# Cool-unitV2.net
KiCad netlist of a schematic drawn in EAGLE
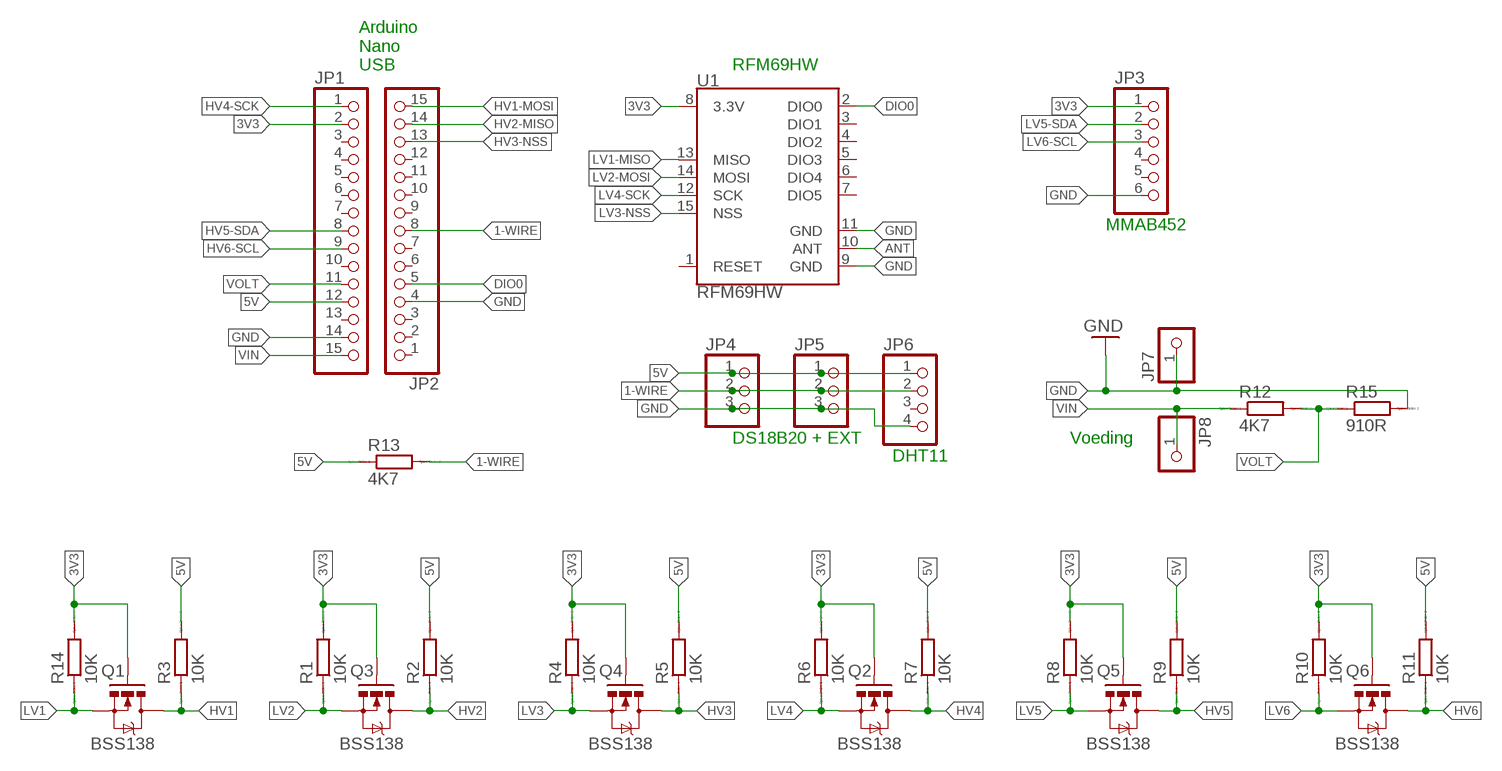
[diagram p0: schematic, sheet 1]

(export (version "E")
  (design (tool "Eeschema 10.0.6"))
  (components
    (comp (ref "JP1")
      (value "PINHD-1X15")
      (footprint "eagle-import:1X15")
      (libsource (lib "eagle-import") (part "PINHD-1X15"))
    )
    (comp (ref "JP2")
      (value "PINHD-1X15")
      (footprint "eagle-import:1X15")
      (libsource (lib "eagle-import") (part "PINHD-1X15"))
    )
    (comp (ref "JP3")
      (value "PINHD-1X6")
      (footprint "eagle-import:1X06")
      (libsource (lib "eagle-import") (part "PINHD-1X6"))
    )
    (comp (ref "JP4")
      (value "PINHD-1X3")
      (footprint "eagle-import:1X03")
      (libsource (lib "eagle-import") (part "PINHD-1X3"))
    )
    (comp (ref "JP5")
      (value "PINHD-1X3")
      (footprint "eagle-import:1X03")
      (libsource (lib "eagle-import") (part "PINHD-1X3"))
    )
    (comp (ref "JP6")
      (value "PINHD-1X4")
      (footprint "eagle-import:1X04")
      (libsource (lib "eagle-import") (part "PINHD-1X4"))
    )
    (comp (ref "JP7")
      (value "PINHD-1X1")
      (footprint "eagle-import:1X01")
      (libsource (lib "eagle-import") (part "PINHD-1X1"))
    )
    (comp (ref "JP8")
      (value "PINHD-1X1")
      (footprint "eagle-import:1X01")
      (libsource (lib "eagle-import") (part "PINHD-1X1"))
    )
    (comp (ref "Q1")
      (value "BSS138")
      (footprint "eagle-import:SOT23-3")
      (libsource (lib "eagle-import") (part "MOSFET-NCHANNELSMD"))
    )
    (comp (ref "Q2")
      (value "BSS138")
      (footprint "eagle-import:SOT23-3")
      (libsource (lib "eagle-import") (part "MOSFET-NCHANNELSMD"))
    )
    (comp (ref "Q3")
      (value "BSS138")
      (footprint "eagle-import:SOT23-3")
      (libsource (lib "eagle-import") (part "MOSFET-NCHANNELSMD"))
    )
    (comp (ref "Q4")
      (value "BSS138")
      (footprint "eagle-import:SOT23-3")
      (libsource (lib "eagle-import") (part "MOSFET-NCHANNELSMD"))
    )
    (comp (ref "Q5")
      (value "BSS138")
      (footprint "eagle-import:SOT23-3")
      (libsource (lib "eagle-import") (part "MOSFET-NCHANNELSMD"))
    )
    (comp (ref "Q6")
      (value "BSS138")
      (footprint "eagle-import:SOT23-3")
      (libsource (lib "eagle-import") (part "MOSFET-NCHANNELSMD"))
    )
    (comp (ref "R1")
      (value "10K")
      (footprint "eagle-import:R3216")
      (libsource (lib "eagle-import") (part "RR3216"))
    )
    (comp (ref "R2")
      (value "10K")
      (footprint "eagle-import:R3216")
      (libsource (lib "eagle-import") (part "RR3216"))
    )
    (comp (ref "R3")
      (value "10K")
      (footprint "eagle-import:R3216")
      (libsource (lib "eagle-import") (part "RR3216"))
    )
    (comp (ref "R4")
      (value "10K")
      (footprint "eagle-import:R3216")
      (libsource (lib "eagle-import") (part "RR3216"))
    )
    (comp (ref "R5")
      (value "10K")
      (footprint "eagle-import:R3216")
      (libsource (lib "eagle-import") (part "RR3216"))
    )
    (comp (ref "R6")
      (value "10K")
      (footprint "eagle-import:R3216")
      (libsource (lib "eagle-import") (part "RR3216"))
    )
    (comp (ref "R7")
      (value "10K")
      (footprint "eagle-import:R3216")
      (libsource (lib "eagle-import") (part "RR3216"))
    )
    (comp (ref "R8")
      (value "10K")
      (footprint "eagle-import:R3216")
      (libsource (lib "eagle-import") (part "RR3216"))
    )
    (comp (ref "R9")
      (value "10K")
      (footprint "eagle-import:R3216")
      (libsource (lib "eagle-import") (part "RR3216"))
    )
    (comp (ref "R10")
      (value "10K")
      (footprint "eagle-import:R3216")
      (libsource (lib "eagle-import") (part "RR3216"))
    )
    (comp (ref "R11")
      (value "10K")
      (footprint "eagle-import:R3216")
      (libsource (lib "eagle-import") (part "RR3216"))
    )
    (comp (ref "R12")
      (value "4K7")
      (footprint "eagle-import:R3216")
      (libsource (lib "eagle-import") (part "RR3216"))
    )
    (comp (ref "R13")
      (value "4K7")
      (footprint "eagle-import:R3216")
      (libsource (lib "eagle-import") (part "RR3216"))
    )
    (comp (ref "R14")
      (value "10K")
      (footprint "eagle-import:R3216")
      (libsource (lib "eagle-import") (part "RR3216"))
    )
    (comp (ref "R15")
      (value "910R")
      (footprint "eagle-import:R3216")
      (libsource (lib "eagle-import") (part "RR3216"))
    )
    (comp (ref "U1")
      (value "RFM69HW")
      (footprint "eagle-import:RFM69W-XXXS2")
      (libsource (lib "eagle-import") (part "RFM69HW"))
    )
  )
  (nets
    (net (code "1") (name "1-WIRE") (class "Default")
      (node (ref "JP2") (pin "8") (pinfunction "8_8") (pintype "passive"))
      (node (ref "JP4") (pin "2") (pinfunction "2_2") (pintype "passive"))
      (node (ref "JP5") (pin "2") (pinfunction "2_2") (pintype "passive"))
      (node (ref "JP6") (pin "2") (pinfunction "2_2") (pintype "passive"))
      (node (ref "R13") (pin "2") (pinfunction "2_2") (pintype "passive"))
    )
    (net (code "2") (name "3V3") (class "Default")
      (node (ref "JP1") (pin "2") (pinfunction "2_2") (pintype "passive"))
      (node (ref "JP3") (pin "1") (pinfunction "1_1") (pintype "passive"))
      (node (ref "Q1") (pin "1") (pinfunction "G_1") (pintype "passive"))
      (node (ref "Q2") (pin "1") (pinfunction "G_1") (pintype "passive"))
      (node (ref "Q3") (pin "1") (pinfunction "G_1") (pintype "passive"))
      (node (ref "Q4") (pin "1") (pinfunction "G_1") (pintype "passive"))
      (node (ref "Q5") (pin "1") (pinfunction "G_1") (pintype "passive"))
      (node (ref "Q6") (pin "1") (pinfunction "G_1") (pintype "passive"))
      (node (ref "R1") (pin "2") (pinfunction "2_2") (pintype "passive"))
      (node (ref "R10") (pin "2") (pinfunction "2_2") (pintype "passive"))
      (node (ref "R14") (pin "2") (pinfunction "2_2") (pintype "passive"))
      (node (ref "R4") (pin "2") (pinfunction "2_2") (pintype "passive"))
      (node (ref "R6") (pin "2") (pinfunction "2_2") (pintype "passive"))
      (node (ref "R8") (pin "2") (pinfunction "2_2") (pintype "passive"))
      (node (ref "U1") (pin "8") (pinfunction "3.3V_8") (pintype "power_in"))
    )
    (net (code "3") (name "5V") (class "Default")
      (node (ref "JP1") (pin "12") (pinfunction "12_12") (pintype "passive"))
      (node (ref "JP4") (pin "1") (pinfunction "1_1") (pintype "passive"))
      (node (ref "JP5") (pin "1") (pinfunction "1_1") (pintype "passive"))
      (node (ref "JP6") (pin "1") (pinfunction "1_1") (pintype "passive"))
      (node (ref "R11") (pin "2") (pinfunction "2_2") (pintype "passive"))
      (node (ref "R13") (pin "1") (pinfunction "1_1") (pintype "passive"))
      (node (ref "R2") (pin "2") (pinfunction "2_2") (pintype "passive"))
      (node (ref "R3") (pin "2") (pinfunction "2_2") (pintype "passive"))
      (node (ref "R5") (pin "2") (pinfunction "2_2") (pintype "passive"))
      (node (ref "R7") (pin "2") (pinfunction "2_2") (pintype "passive"))
      (node (ref "R9") (pin "2") (pinfunction "2_2") (pintype "passive"))
    )
    (net (code "4") (name "ANT") (class "Default")
      (node (ref "U1") (pin "10") (pinfunction "ANT_10") (pintype "passive"))
    )
    (net (code "5") (name "DIO0") (class "Default")
      (node (ref "JP2") (pin "5") (pinfunction "5_5") (pintype "passive"))
      (node (ref "U1") (pin "2") (pinfunction "DIO0_2") (pintype "bidirectional"))
    )
    (net (code "6") (name "GND") (class "Default")
      (node (ref "JP1") (pin "14") (pinfunction "14_14") (pintype "passive"))
      (node (ref "JP2") (pin "4") (pinfunction "4_4") (pintype "passive"))
      (node (ref "JP3") (pin "6") (pinfunction "6_6") (pintype "passive"))
      (node (ref "JP4") (pin "3") (pinfunction "3_3") (pintype "passive"))
      (node (ref "JP5") (pin "3") (pinfunction "3_3") (pintype "passive"))
      (node (ref "JP6") (pin "4") (pinfunction "4_4") (pintype "passive"))
      (node (ref "JP7") (pin "1") (pinfunction "1_1") (pintype "passive"))
      (node (ref "R15") (pin "2") (pinfunction "2_2") (pintype "passive"))
      (node (ref "U1") (pin "11") (pinfunction "GND_11") (pintype "power_in"))
      (node (ref "U1") (pin "9") (pinfunction "GND_9") (pintype "power_in"))
    )
    (net (code "7") (name "HV1") (class "Default")
      (node (ref "JP2") (pin "15") (pinfunction "15_15") (pintype "passive"))
      (node (ref "Q1") (pin "3") (pinfunction "D_3") (pintype "passive"))
      (node (ref "R3") (pin "1") (pinfunction "1_1") (pintype "passive"))
    )
    (net (code "8") (name "HV2") (class "Default")
      (node (ref "JP2") (pin "14") (pinfunction "14_14") (pintype "passive"))
      (node (ref "Q3") (pin "3") (pinfunction "D_3") (pintype "passive"))
      (node (ref "R2") (pin "1") (pinfunction "1_1") (pintype "passive"))
    )
    (net (code "9") (name "HV3") (class "Default")
      (node (ref "JP2") (pin "13") (pinfunction "13_13") (pintype "passive"))
      (node (ref "Q4") (pin "3") (pinfunction "D_3") (pintype "passive"))
      (node (ref "R5") (pin "1") (pinfunction "1_1") (pintype "passive"))
    )
    (net (code "10") (name "HV4") (class "Default")
      (node (ref "JP1") (pin "1") (pinfunction "1_1") (pintype "passive"))
      (node (ref "Q2") (pin "3") (pinfunction "D_3") (pintype "passive"))
      (node (ref "R7") (pin "1") (pinfunction "1_1") (pintype "passive"))
    )
    (net (code "11") (name "HV5") (class "Default")
      (node (ref "JP1") (pin "8") (pinfunction "8_8") (pintype "passive"))
      (node (ref "Q5") (pin "3") (pinfunction "D_3") (pintype "passive"))
      (node (ref "R9") (pin "1") (pinfunction "1_1") (pintype "passive"))
    )
    (net (code "12") (name "HV6") (class "Default")
      (node (ref "JP1") (pin "9") (pinfunction "9_9") (pintype "passive"))
      (node (ref "Q6") (pin "3") (pinfunction "D_3") (pintype "passive"))
      (node (ref "R11") (pin "1") (pinfunction "1_1") (pintype "passive"))
    )
    (net (code "13") (name "LV1") (class "Default")
      (node (ref "Q1") (pin "2") (pinfunction "S_2") (pintype "passive"))
      (node (ref "R14") (pin "1") (pinfunction "1_1") (pintype "passive"))
      (node (ref "U1") (pin "13") (pinfunction "MISO_13") (pintype "bidirectional"))
    )
    (net (code "14") (name "LV2") (class "Default")
      (node (ref "Q3") (pin "2") (pinfunction "S_2") (pintype "passive"))
      (node (ref "R1") (pin "1") (pinfunction "1_1") (pintype "passive"))
      (node (ref "U1") (pin "14") (pinfunction "MOSI_14") (pintype "input"))
    )
    (net (code "15") (name "LV3") (class "Default")
      (node (ref "Q4") (pin "2") (pinfunction "S_2") (pintype "passive"))
      (node (ref "R4") (pin "1") (pinfunction "1_1") (pintype "passive"))
      (node (ref "U1") (pin "15") (pinfunction "NSS_15") (pintype "input"))
    )
    (net (code "16") (name "LV4") (class "Default")
      (node (ref "Q2") (pin "2") (pinfunction "S_2") (pintype "passive"))
      (node (ref "R6") (pin "1") (pinfunction "1_1") (pintype "passive"))
      (node (ref "U1") (pin "12") (pinfunction "SCK_12") (pintype "input"))
    )
    (net (code "17") (name "LV5") (class "Default")
      (node (ref "JP3") (pin "2") (pinfunction "2_2") (pintype "passive"))
      (node (ref "Q5") (pin "2") (pinfunction "S_2") (pintype "passive"))
      (node (ref "R8") (pin "1") (pinfunction "1_1") (pintype "passive"))
    )
    (net (code "18") (name "LV6") (class "Default")
      (node (ref "JP3") (pin "3") (pinfunction "3_3") (pintype "passive"))
      (node (ref "Q6") (pin "2") (pinfunction "S_2") (pintype "passive"))
      (node (ref "R10") (pin "1") (pinfunction "1_1") (pintype "passive"))
    )
    (net (code "19") (name "VIN") (class "Default")
      (node (ref "JP1") (pin "15") (pinfunction "15_15") (pintype "passive"))
      (node (ref "JP8") (pin "1") (pinfunction "1_1") (pintype "passive"))
      (node (ref "R12") (pin "1") (pinfunction "1_1") (pintype "passive"))
    )
    (net (code "20") (name "VOLT") (class "Default")
      (node (ref "JP1") (pin "11") (pinfunction "11_11") (pintype "passive"))
      (node (ref "R12") (pin "2") (pinfunction "2_2") (pintype "passive"))
      (node (ref "R15") (pin "1") (pinfunction "1_1") (pintype "passive"))
    )
    (net (code "21") (name "unconnected-(JP1-Pad3)") (class "Default")
      (node (ref "JP1") (pin "3") (pinfunction "3_3") (pintype "passive"))
    )
    (net (code "22") (name "unconnected-(JP1-Pad4)") (class "Default")
      (node (ref "JP1") (pin "4") (pinfunction "4_4") (pintype "passive"))
    )
    (net (code "23") (name "unconnected-(JP1-Pad5)") (class "Default")
      (node (ref "JP1") (pin "5") (pinfunction "5_5") (pintype "passive"))
    )
    (net (code "24") (name "unconnected-(JP1-Pad6)") (class "Default")
      (node (ref "JP1") (pin "6") (pinfunction "6_6") (pintype "passive"))
    )
    (net (code "25") (name "unconnected-(JP1-Pad7)") (class "Default")
      (node (ref "JP1") (pin "7") (pinfunction "7_7") (pintype "passive"))
    )
    (net (code "26") (name "unconnected-(JP1-Pad10)") (class "Default")
      (node (ref "JP1") (pin "10") (pinfunction "10_10") (pintype "passive"))
    )
    (net (code "27") (name "unconnected-(JP1-Pad13)") (class "Default")
      (node (ref "JP1") (pin "13") (pinfunction "13_13") (pintype "passive"))
    )
    (net (code "28") (name "unconnected-(JP2-Pad1)") (class "Default")
      (node (ref "JP2") (pin "1") (pinfunction "1_1") (pintype "passive"))
    )
    (net (code "29") (name "unconnected-(JP2-Pad2)") (class "Default")
      (node (ref "JP2") (pin "2") (pinfunction "2_2") (pintype "passive"))
    )
    (net (code "30") (name "unconnected-(JP2-Pad3)") (class "Default")
      (node (ref "JP2") (pin "3") (pinfunction "3_3") (pintype "passive"))
    )
    (net (code "31") (name "unconnected-(JP2-Pad6)") (class "Default")
      (node (ref "JP2") (pin "6") (pinfunction "6_6") (pintype "passive"))
    )
    (net (code "32") (name "unconnected-(JP2-Pad7)") (class "Default")
      (node (ref "JP2") (pin "7") (pinfunction "7_7") (pintype "passive"))
    )
    (net (code "33") (name "unconnected-(JP2-Pad9)") (class "Default")
      (node (ref "JP2") (pin "9") (pinfunction "9_9") (pintype "passive"))
    )
    (net (code "34") (name "unconnected-(JP2-Pad10)") (class "Default")
      (node (ref "JP2") (pin "10") (pinfunction "10_10") (pintype "passive"))
    )
    (net (code "35") (name "unconnected-(JP2-Pad11)") (class "Default")
      (node (ref "JP2") (pin "11") (pinfunction "11_11") (pintype "passive"))
    )
    (net (code "36") (name "unconnected-(JP2-Pad12)") (class "Default")
      (node (ref "JP2") (pin "12") (pinfunction "12_12") (pintype "passive"))
    )
    (net (code "37") (name "unconnected-(JP3-Pad4)") (class "Default")
      (node (ref "JP3") (pin "4") (pinfunction "4_4") (pintype "passive"))
    )
    (net (code "38") (name "unconnected-(JP3-Pad5)") (class "Default")
      (node (ref "JP3") (pin "5") (pinfunction "5_5") (pintype "passive"))
    )
    (net (code "39") (name "unconnected-(JP6-Pad3)") (class "Default")
      (node (ref "JP6") (pin "3") (pinfunction "3_3") (pintype "passive"))
    )
    (net (code "40") (name "unconnected-(U1-DIO1-Pad3)") (class "Default")
      (node (ref "U1") (pin "3") (pinfunction "DIO1_3") (pintype "bidirectional"))
    )
    (net (code "41") (name "unconnected-(U1-DIO2-Pad4)") (class "Default")
      (node (ref "U1") (pin "4") (pinfunction "DIO2_4") (pintype "bidirectional"))
    )
    (net (code "42") (name "unconnected-(U1-DIO3-Pad5)") (class "Default")
      (node (ref "U1") (pin "5") (pinfunction "DIO3_5") (pintype "bidirectional"))
    )
    (net (code "43") (name "unconnected-(U1-DIO4-Pad6)") (class "Default")
      (node (ref "U1") (pin "6") (pinfunction "DIO4_6") (pintype "bidirectional"))
    )
    (net (code "44") (name "unconnected-(U1-DIO5-Pad7)") (class "Default")
      (node (ref "U1") (pin "7") (pinfunction "DIO5_7") (pintype "bidirectional"))
    )
    (net (code "45") (name "unconnected-(U1-RESET-Pad1)") (class "Default")
      (node (ref "U1") (pin "1") (pinfunction "RESET_1") (pintype "input"))
    )
  )
)
